# Input_Connectors.net
KiCad netlist of a schematic drawn in Altium Designer
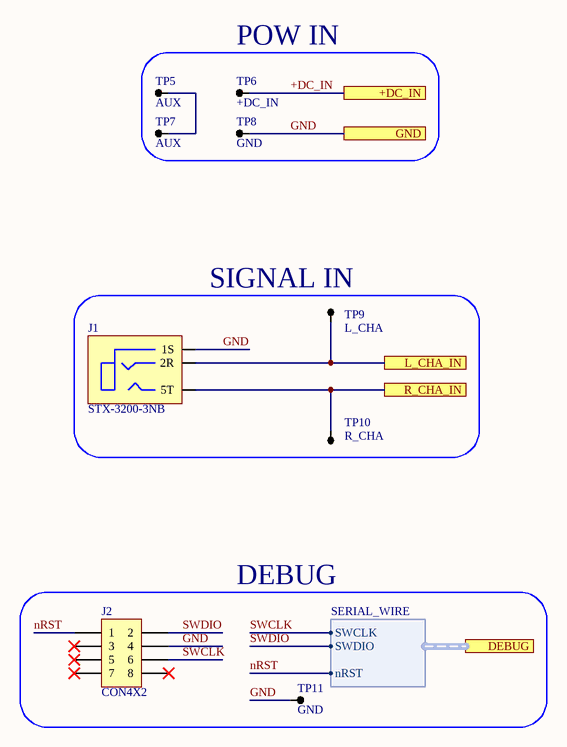
[diagram p0: Input_Connectors.SchDoc]

(export (version "E")
  (design (tool "Eeschema 10.0.6"))
  (components
    (comp (ref "J1")
      (value "STX-3200-3NB")
      (footprint "JACK-3.5-3POS")
      (libsource (lib "LIB2022 - Connectors") (part "STX-3200-3NB"))
    )
    (comp (ref "J2")
      (value "CON4X2")
      (footprint "SIP4X2")
      (libsource (lib "LIB2022 - Connectors") (part "CON4X2"))
    )
    (comp (ref "TP5")
      (value "AUX")
      (footprint "534-5280")
      (libsource (lib "LIB2022 - Mechanicals") (part "TP-CLAW"))
    )
    (comp (ref "TP6")
      (value "+DC_IN")
      (footprint "534-5280")
      (libsource (lib "LIB2022 - Mechanicals") (part "TP-CLAW"))
    )
    (comp (ref "TP7")
      (value "AUX")
      (footprint "534-5280")
      (libsource (lib "LIB2022 - Mechanicals") (part "TP-CLAW"))
    )
    (comp (ref "TP8")
      (value "GND")
      (footprint "534-5280")
      (libsource (lib "LIB2022 - Mechanicals") (part "TP-CLAW"))
    )
    (comp (ref "TP9")
      (value "L_CHA")
      (footprint "534-5280")
      (libsource (lib "LIB2022 - Mechanicals") (part "TP-CLAW"))
    )
    (comp (ref "TP10")
      (value "R_CHA")
      (footprint "534-5280")
      (libsource (lib "LIB2022 - Mechanicals") (part "TP-CLAW"))
    )
    (comp (ref "TP11")
      (value "GND")
      (footprint "534-5280")
      (libsource (lib "LIB2022 - Mechanicals") (part "TP-CLAW"))
    )
  )
  (nets
    (net (code "2") (name "/+DC_IN") (class "Default")
      (node (ref "TP6") (pin "1") (pinfunction "1_1") (pintype "passive"))
    )
    (net (code "3") (name "/GND") (class "Default")
      (node (ref "J1") (pin "1S") (pinfunction "1S_1S") (pintype "passive"))
      (node (ref "J2") (pin "4") (pinfunction "4_4") (pintype "passive"))
      (node (ref "TP11") (pin "1") (pinfunction "1_1") (pintype "passive"))
      (node (ref "TP8") (pin "1") (pinfunction "1_1") (pintype "passive"))
    )
    (net (code "4") (name "/L_CHA_IN") (class "Default")
      (node (ref "J1") (pin "2R") (pinfunction "2R_2R") (pintype "passive"))
      (node (ref "TP9") (pin "1") (pinfunction "1_1") (pintype "passive"))
    )
    (net (code "5") (name "/R_CHA_IN") (class "Default")
      (node (ref "J1") (pin "5T") (pinfunction "5T_5T") (pintype "passive"))
      (node (ref "TP10") (pin "1") (pinfunction "1_1") (pintype "passive"))
    )
    (net (code "6") (name "/SWCLK") (class "Default")
      (node (ref "J2") (pin "6") (pinfunction "6_6") (pintype "passive"))
    )
    (net (code "7") (name "/SWDIO") (class "Default")
      (node (ref "J2") (pin "2") (pinfunction "2_2") (pintype "passive"))
    )
    (net (code "8") (name "/nRST") (class "Default")
      (node (ref "J2") (pin "1") (pinfunction "1_1") (pintype "passive"))
    )
    (net (code "10") (name "Net-(TP5-Pad1)") (class "Default")
      (node (ref "TP5") (pin "1") (pinfunction "1_1") (pintype "passive"))
      (node (ref "TP7") (pin "1") (pinfunction "1_1") (pintype "passive"))
    )
    (net (code "11") (name "unconnected-(J2-Pad3)") (class "Default")
      (node (ref "J2") (pin "3") (pinfunction "3_3") (pintype "passive+no_connect"))
    )
    (net (code "12") (name "unconnected-(J2-Pad5)") (class "Default")
      (node (ref "J2") (pin "5") (pinfunction "5_5") (pintype "passive+no_connect"))
    )
    (net (code "13") (name "unconnected-(J2-Pad7)") (class "Default")
      (node (ref "J2") (pin "7") (pinfunction "7_7") (pintype "passive+no_connect"))
    )
    (net (code "14") (name "unconnected-(J2-Pad8)") (class "Default")
      (node (ref "J2") (pin "8") (pinfunction "8_8") (pintype "passive+no_connect"))
    )
  )
)
